# sensor.net
KiCad netlist of a schematic drawn in EAGLE
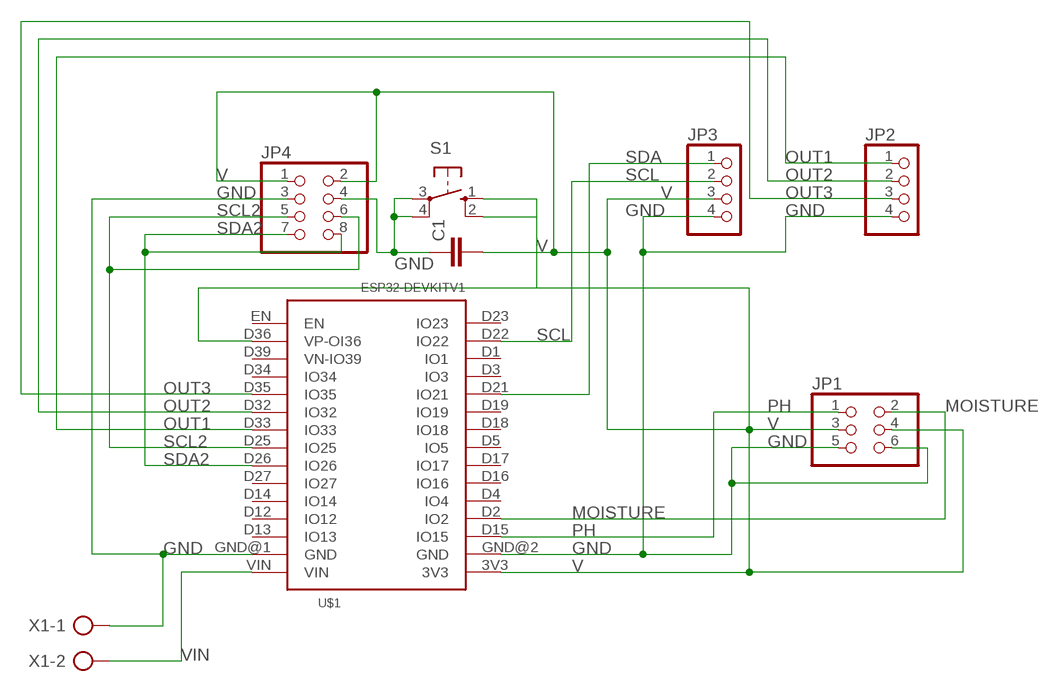
[diagram p0: schematic, sheet 1]

(export (version "E")
  (design (tool "Eeschema 10.0.6"))
  (components
    (comp (ref "C1")
      (value "C-EU050-030X075")
      (footprint "eagle-import:C050-030X075")
      (libsource (lib "eagle-import") (part "C-EU050-030X075"))
    )
    (comp (ref "JP1")
      (value "PINHD-2X3")
      (footprint "eagle-import:2X03")
      (libsource (lib "eagle-import") (part "PINHD-2X3"))
    )
    (comp (ref "JP2")
      (value "PINHD-1X4")
      (footprint "eagle-import:1X04")
      (libsource (lib "eagle-import") (part "PINHD-1X4"))
    )
    (comp (ref "JP3")
      (value "PINHD-1X4")
      (footprint "eagle-import:1X04")
      (libsource (lib "eagle-import") (part "PINHD-1X4"))
    )
    (comp (ref "JP4")
      (value "PINHD-2X4")
      (footprint "eagle-import:2X04")
      (libsource (lib "eagle-import") (part "PINHD-2X4"))
    )
    (comp (ref "S1")
      (value "10-XX")
      (footprint "eagle-import:B3F-10XX")
      (fields (field (name "MPN") "B3F-1000"))
      (libsource (lib "eagle-import") (part "10-XX"))
    )
    (comp (ref "U$1")
      (value "ESP32DEVKITV1")
      (footprint "eagle-import:ESP32-DEVKITV1")
      (libsource (lib "eagle-import") (part "ESP32DEVKITV1"))
    )
    (comp (ref "X1")
      (value "AK300/2")
      (footprint "eagle-import:AK300_2")
      (libsource (lib "eagle-import") (part "AK300/2"))
    )
  )
  (nets
    (net (code "1") (name "/GND") (class "Default")
      (node (ref "C1") (pin "1") (pinfunction "1_1") (pintype "passive"))
      (node (ref "JP1") (pin "5") (pinfunction "5_5") (pintype "passive"))
      (node (ref "JP1") (pin "6") (pinfunction "6_6") (pintype "passive"))
      (node (ref "JP2") (pin "4") (pinfunction "4_4") (pintype "passive"))
      (node (ref "JP3") (pin "4") (pinfunction "4_4") (pintype "passive"))
      (node (ref "JP4") (pin "3") (pinfunction "3_3") (pintype "passive"))
      (node (ref "JP4") (pin "4") (pinfunction "4_4") (pintype "passive"))
      (node (ref "S1") (pin "3") (pinfunction "P_3") (pintype "passive"))
      (node (ref "S1") (pin "4") (pinfunction "P1_4") (pintype "passive"))
      (node (ref "U$1") (pin "GND@1") (pinfunction "GND_GND@1") (pintype "bidirectional"))
      (node (ref "U$1") (pin "GND@2") (pinfunction "GND_GND@2") (pintype "bidirectional"))
      (node (ref "X1") (pin "1") (pinfunction "KL_1") (pintype "passive"))
    )
    (net (code "2") (name "/MOISTURE") (class "Default")
      (node (ref "JP1") (pin "2") (pinfunction "2_2") (pintype "passive"))
      (node (ref "U$1") (pin "D2") (pinfunction "IO2_D2") (pintype "bidirectional"))
    )
    (net (code "3") (name "/OUT1") (class "Default")
      (node (ref "JP2") (pin "1") (pinfunction "1_1") (pintype "passive"))
      (node (ref "U$1") (pin "D33") (pinfunction "IO33_D33") (pintype "bidirectional"))
    )
    (net (code "4") (name "/OUT2") (class "Default")
      (node (ref "JP2") (pin "2") (pinfunction "2_2") (pintype "passive"))
      (node (ref "U$1") (pin "D32") (pinfunction "IO32_D32") (pintype "bidirectional"))
    )
    (net (code "5") (name "/OUT3") (class "Default")
      (node (ref "JP2") (pin "3") (pinfunction "3_3") (pintype "passive"))
      (node (ref "U$1") (pin "D35") (pinfunction "IO35_D35") (pintype "bidirectional"))
    )
    (net (code "6") (name "/PH") (class "Default")
      (node (ref "JP1") (pin "1") (pinfunction "1_1") (pintype "passive"))
      (node (ref "U$1") (pin "D15") (pinfunction "IO15_D15") (pintype "bidirectional"))
    )
    (net (code "7") (name "/SCL") (class "Default")
      (node (ref "JP3") (pin "2") (pinfunction "2_2") (pintype "passive"))
      (node (ref "U$1") (pin "D22") (pinfunction "IO22_D22") (pintype "bidirectional"))
    )
    (net (code "8") (name "/SCL2") (class "Default")
      (node (ref "JP4") (pin "5") (pinfunction "5_5") (pintype "passive"))
      (node (ref "JP4") (pin "6") (pinfunction "6_6") (pintype "passive"))
      (node (ref "U$1") (pin "D25") (pinfunction "IO25_D25") (pintype "bidirectional"))
    )
    (net (code "9") (name "/SDA") (class "Default")
      (node (ref "JP3") (pin "1") (pinfunction "1_1") (pintype "passive"))
      (node (ref "U$1") (pin "D21") (pinfunction "IO21_D21") (pintype "bidirectional"))
    )
    (net (code "10") (name "/SDA2") (class "Default")
      (node (ref "JP4") (pin "7") (pinfunction "7_7") (pintype "passive"))
      (node (ref "JP4") (pin "8") (pinfunction "8_8") (pintype "passive"))
      (node (ref "U$1") (pin "D26") (pinfunction "IO26_D26") (pintype "bidirectional"))
    )
    (net (code "11") (name "/V") (class "Default")
      (node (ref "C1") (pin "2") (pinfunction "2_2") (pintype "passive"))
      (node (ref "JP1") (pin "3") (pinfunction "3_3") (pintype "passive"))
      (node (ref "JP1") (pin "4") (pinfunction "4_4") (pintype "passive"))
      (node (ref "JP3") (pin "3") (pinfunction "3_3") (pintype "passive"))
      (node (ref "JP4") (pin "1") (pinfunction "1_1") (pintype "passive"))
      (node (ref "JP4") (pin "2") (pinfunction "2_2") (pintype "passive"))
      (node (ref "S1") (pin "1") (pinfunction "S_1") (pintype "passive"))
      (node (ref "U$1") (pin "3V3") (pinfunction "3V3_3V3") (pintype "bidirectional"))
      (node (ref "U$1") (pin "D36") (pinfunction "VP-OI36_D36") (pintype "bidirectional"))
    )
    (net (code "12") (name "/VIN") (class "Default")
      (node (ref "U$1") (pin "VIN") (pinfunction "VIN_VIN") (pintype "bidirectional"))
      (node (ref "X1") (pin "2") (pinfunction "KL_2") (pintype "passive"))
    )
    (net (code "13") (name "unconnected-(S1-S1-Pad2)") (class "Default")
      (node (ref "S1") (pin "2") (pinfunction "S1_2") (pintype "passive"))
    )
    (net (code "14") (name "unconnected-(U$1-IO1-PadD1)") (class "Default")
      (node (ref "U$1") (pin "D1") (pinfunction "IO1_D1") (pintype "bidirectional"))
    )
    (net (code "15") (name "unconnected-(U$1-IO3-PadD3)") (class "Default")
      (node (ref "U$1") (pin "D3") (pinfunction "IO3_D3") (pintype "bidirectional"))
    )
    (net (code "16") (name "unconnected-(U$1-IO4-PadD4)") (class "Default")
      (node (ref "U$1") (pin "D4") (pinfunction "IO4_D4") (pintype "bidirectional"))
    )
    (net (code "17") (name "unconnected-(U$1-IO5-PadD5)") (class "Default")
      (node (ref "U$1") (pin "D5") (pinfunction "IO5_D5") (pintype "bidirectional"))
    )
    (net (code "18") (name "unconnected-(U$1-IO12-PadD12)") (class "Default")
      (node (ref "U$1") (pin "D12") (pinfunction "IO12_D12") (pintype "bidirectional"))
    )
    (net (code "19") (name "unconnected-(U$1-IO13-PadD13)") (class "Default")
      (node (ref "U$1") (pin "D13") (pinfunction "IO13_D13") (pintype "bidirectional"))
    )
    (net (code "20") (name "unconnected-(U$1-IO14-PadD14)") (class "Default")
      (node (ref "U$1") (pin "D14") (pinfunction "IO14_D14") (pintype "bidirectional"))
    )
    (net (code "21") (name "unconnected-(U$1-IO16-PadD16)") (class "Default")
      (node (ref "U$1") (pin "D16") (pinfunction "IO16_D16") (pintype "bidirectional"))
    )
    (net (code "22") (name "unconnected-(U$1-IO17-PadD17)") (class "Default")
      (node (ref "U$1") (pin "D17") (pinfunction "IO17_D17") (pintype "bidirectional"))
    )
    (net (code "23") (name "unconnected-(U$1-IO18-PadD18)") (class "Default")
      (node (ref "U$1") (pin "D18") (pinfunction "IO18_D18") (pintype "bidirectional"))
    )
    (net (code "24") (name "unconnected-(U$1-IO19-PadD19)") (class "Default")
      (node (ref "U$1") (pin "D19") (pinfunction "IO19_D19") (pintype "bidirectional"))
    )
    (net (code "25") (name "unconnected-(U$1-IO23-PadD23)") (class "Default")
      (node (ref "U$1") (pin "D23") (pinfunction "IO23_D23") (pintype "bidirectional"))
    )
    (net (code "26") (name "unconnected-(U$1-IO27-PadD27)") (class "Default")
      (node (ref "U$1") (pin "D27") (pinfunction "IO27_D27") (pintype "bidirectional"))
    )
    (net (code "27") (name "unconnected-(U$1-IO34-PadD34)") (class "Default")
      (node (ref "U$1") (pin "D34") (pinfunction "IO34_D34") (pintype "bidirectional"))
    )
    (net (code "28") (name "unconnected-(U$1-PadEN)") (class "Default")
      (node (ref "U$1") (pin "EN") (pinfunction "EN_EN") (pintype "bidirectional"))
    )
    (net (code "29") (name "unconnected-(U$1-VN-IO39-PadD39)") (class "Default")
      (node (ref "U$1") (pin "D39") (pinfunction "VN-IO39_D39") (pintype "bidirectional"))
    )
  )
)
